# L1.net
KiCad netlist of a schematic drawn in EAGLE
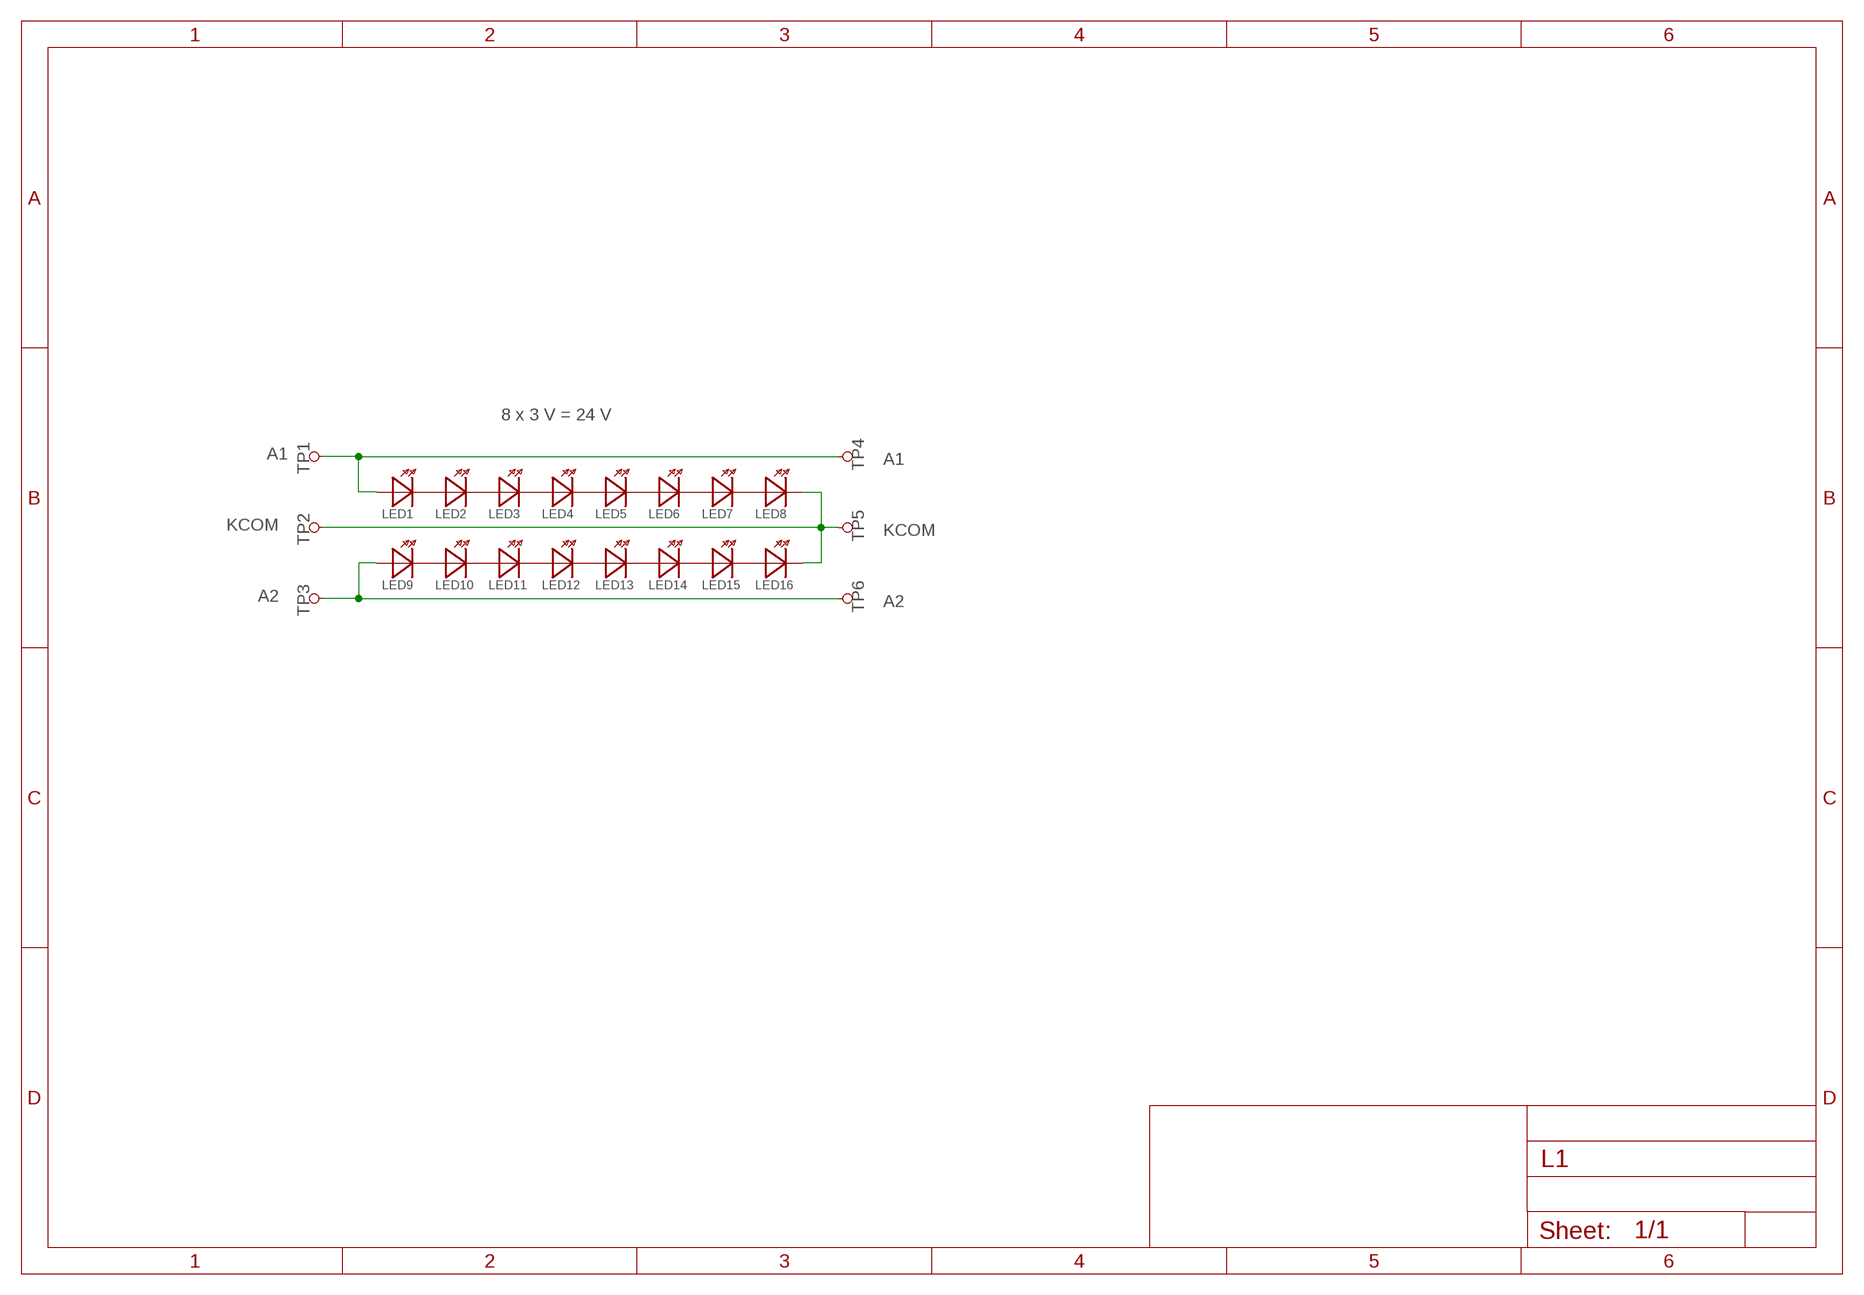
[diagram p0: schematic, sheet 1]

(export (version "E")
  (design (tool "Eeschema 10.0.6"))
  (components
    (comp (ref "LED1")
      (value "LED_JE2835")
      (footprint "eagle-import:LED_JE2835")
      (libsource (lib "eagle-import") (part "LED_JE2835"))
    )
    (comp (ref "LED2")
      (value "LED_JE2835")
      (footprint "eagle-import:LED_JE2835")
      (libsource (lib "eagle-import") (part "LED_JE2835"))
    )
    (comp (ref "LED3")
      (value "LED_JE2835")
      (footprint "eagle-import:LED_JE2835")
      (libsource (lib "eagle-import") (part "LED_JE2835"))
    )
    (comp (ref "LED4")
      (value "LED_JE2835")
      (footprint "eagle-import:LED_JE2835")
      (libsource (lib "eagle-import") (part "LED_JE2835"))
    )
    (comp (ref "LED5")
      (value "LED_JE2835")
      (footprint "eagle-import:LED_JE2835")
      (libsource (lib "eagle-import") (part "LED_JE2835"))
    )
    (comp (ref "LED6")
      (value "LED_JE2835")
      (footprint "eagle-import:LED_JE2835")
      (libsource (lib "eagle-import") (part "LED_JE2835"))
    )
    (comp (ref "LED7")
      (value "LED_JE2835")
      (footprint "eagle-import:LED_JE2835")
      (libsource (lib "eagle-import") (part "LED_JE2835"))
    )
    (comp (ref "LED8")
      (value "LED_JE2835")
      (footprint "eagle-import:LED_JE2835")
      (libsource (lib "eagle-import") (part "LED_JE2835"))
    )
    (comp (ref "LED9")
      (value "LED_JE2835")
      (footprint "eagle-import:LED_JE2835")
      (libsource (lib "eagle-import") (part "LED_JE2835"))
    )
    (comp (ref "LED10")
      (value "LED_JE2835")
      (footprint "eagle-import:LED_JE2835")
      (libsource (lib "eagle-import") (part "LED_JE2835"))
    )
    (comp (ref "LED11")
      (value "LED_JE2835")
      (footprint "eagle-import:LED_JE2835")
      (libsource (lib "eagle-import") (part "LED_JE2835"))
    )
    (comp (ref "LED12")
      (value "LED_JE2835")
      (footprint "eagle-import:LED_JE2835")
      (libsource (lib "eagle-import") (part "LED_JE2835"))
    )
    (comp (ref "LED13")
      (value "LED_JE2835")
      (footprint "eagle-import:LED_JE2835")
      (libsource (lib "eagle-import") (part "LED_JE2835"))
    )
    (comp (ref "LED14")
      (value "LED_JE2835")
      (footprint "eagle-import:LED_JE2835")
      (libsource (lib "eagle-import") (part "LED_JE2835"))
    )
    (comp (ref "LED15")
      (value "LED_JE2835")
      (footprint "eagle-import:LED_JE2835")
      (libsource (lib "eagle-import") (part "LED_JE2835"))
    )
    (comp (ref "LED16")
      (value "LED_JE2835")
      (footprint "eagle-import:LED_JE2835")
      (libsource (lib "eagle-import") (part "LED_JE2835"))
    )
    (comp (ref "TP1")
      (value "A1")
      (footprint "eagle-import:PAD_4X2.2MM")
      (libsource (lib "eagle-import") (part "TP_4X2.2MM"))
    )
    (comp (ref "TP2")
      (value "KCOM")
      (footprint "eagle-import:PAD_4X2.2MM")
      (libsource (lib "eagle-import") (part "TP_4X2.2MM"))
    )
    (comp (ref "TP3")
      (value "A2")
      (footprint "eagle-import:PAD_4X2.2MM")
      (libsource (lib "eagle-import") (part "TP_4X2.2MM"))
    )
    (comp (ref "TP4")
      (value "A1")
      (footprint "eagle-import:PAD_4X2.2MM")
      (libsource (lib "eagle-import") (part "TP_4X2.2MM"))
    )
    (comp (ref "TP5")
      (value "KCOM")
      (footprint "eagle-import:PAD_4X2.2MM")
      (libsource (lib "eagle-import") (part "TP_4X2.2MM"))
    )
    (comp (ref "TP6")
      (value "A2")
      (footprint "eagle-import:PAD_4X2.2MM")
      (libsource (lib "eagle-import") (part "TP_4X2.2MM"))
    )
  )
  (nets
    (net (code "1") (name "/A1") (class "Default")
      (node (ref "LED1") (pin "1") (pinfunction "A_1") (pintype "passive"))
      (node (ref "TP1") (pin "1") (pinfunction "1_1") (pintype "bidirectional"))
      (node (ref "TP4") (pin "1") (pinfunction "1_1") (pintype "bidirectional"))
    )
    (net (code "2") (name "/A2") (class "Default")
      (node (ref "LED9") (pin "1") (pinfunction "A_1") (pintype "passive"))
      (node (ref "TP3") (pin "1") (pinfunction "1_1") (pintype "bidirectional"))
      (node (ref "TP6") (pin "1") (pinfunction "1_1") (pintype "bidirectional"))
    )
    (net (code "3") (name "/KCOM") (class "Default")
      (node (ref "LED16") (pin "2") (pinfunction "K_2") (pintype "passive"))
      (node (ref "LED8") (pin "2") (pinfunction "K_2") (pintype "passive"))
      (node (ref "TP2") (pin "1") (pinfunction "1_1") (pintype "bidirectional"))
      (node (ref "TP5") (pin "1") (pinfunction "1_1") (pintype "bidirectional"))
    )
    (net (code "4") (name "Net-(LED1-K)") (class "Default")
      (node (ref "LED1") (pin "2") (pinfunction "K_2") (pintype "passive"))
      (node (ref "LED2") (pin "1") (pinfunction "A_1") (pintype "passive"))
    )
    (net (code "5") (name "Net-(LED2-K)") (class "Default")
      (node (ref "LED2") (pin "2") (pinfunction "K_2") (pintype "passive"))
      (node (ref "LED3") (pin "1") (pinfunction "A_1") (pintype "passive"))
    )
    (net (code "6") (name "Net-(LED3-K)") (class "Default")
      (node (ref "LED3") (pin "2") (pinfunction "K_2") (pintype "passive"))
      (node (ref "LED4") (pin "1") (pinfunction "A_1") (pintype "passive"))
    )
    (net (code "7") (name "Net-(LED4-K)") (class "Default")
      (node (ref "LED4") (pin "2") (pinfunction "K_2") (pintype "passive"))
      (node (ref "LED5") (pin "1") (pinfunction "A_1") (pintype "passive"))
    )
    (net (code "8") (name "Net-(LED5-K)") (class "Default")
      (node (ref "LED5") (pin "2") (pinfunction "K_2") (pintype "passive"))
      (node (ref "LED6") (pin "1") (pinfunction "A_1") (pintype "passive"))
    )
    (net (code "9") (name "Net-(LED6-K)") (class "Default")
      (node (ref "LED6") (pin "2") (pinfunction "K_2") (pintype "passive"))
      (node (ref "LED7") (pin "1") (pinfunction "A_1") (pintype "passive"))
    )
    (net (code "10") (name "Net-(LED7-K)") (class "Default")
      (node (ref "LED7") (pin "2") (pinfunction "K_2") (pintype "passive"))
      (node (ref "LED8") (pin "1") (pinfunction "A_1") (pintype "passive"))
    )
    (net (code "11") (name "Net-(LED10-A)") (class "Default")
      (node (ref "LED10") (pin "1") (pinfunction "A_1") (pintype "passive"))
      (node (ref "LED9") (pin "2") (pinfunction "K_2") (pintype "passive"))
    )
    (net (code "12") (name "Net-(LED10-K)") (class "Default")
      (node (ref "LED10") (pin "2") (pinfunction "K_2") (pintype "passive"))
      (node (ref "LED11") (pin "1") (pinfunction "A_1") (pintype "passive"))
    )
    (net (code "13") (name "Net-(LED11-K)") (class "Default")
      (node (ref "LED11") (pin "2") (pinfunction "K_2") (pintype "passive"))
      (node (ref "LED12") (pin "1") (pinfunction "A_1") (pintype "passive"))
    )
    (net (code "14") (name "Net-(LED12-K)") (class "Default")
      (node (ref "LED12") (pin "2") (pinfunction "K_2") (pintype "passive"))
      (node (ref "LED13") (pin "1") (pinfunction "A_1") (pintype "passive"))
    )
    (net (code "15") (name "Net-(LED13-K)") (class "Default")
      (node (ref "LED13") (pin "2") (pinfunction "K_2") (pintype "passive"))
      (node (ref "LED14") (pin "1") (pinfunction "A_1") (pintype "passive"))
    )
    (net (code "16") (name "Net-(LED14-K)") (class "Default")
      (node (ref "LED14") (pin "2") (pinfunction "K_2") (pintype "passive"))
      (node (ref "LED15") (pin "1") (pinfunction "A_1") (pintype "passive"))
    )
    (net (code "17") (name "Net-(LED15-K)") (class "Default")
      (node (ref "LED15") (pin "2") (pinfunction "K_2") (pintype "passive"))
      (node (ref "LED16") (pin "1") (pinfunction "A_1") (pintype "passive"))
    )
  )
)
